# placa_tampa.net
KiCad netlist of a schematic drawn in EAGLE
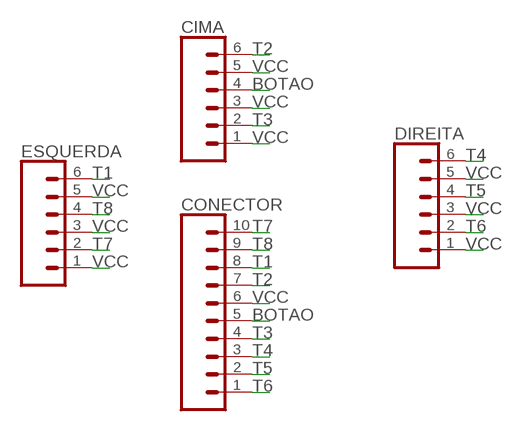
[diagram p0: schematic, sheet 1]

(export (version "E")
  (design (tool "Eeschema 10.0.6"))
  (components
    (comp (ref "CIMA")
      (value "CONN_06SILK_FEMALE_PTH")
      (footprint "eagle-import:1X06")
      (libsource (lib "eagle-import") (part "CONN_06SILK_FEMALE_PTH"))
    )
    (comp (ref "CONECTOR")
      (value "CONN_10\"")
      (footprint "eagle-import:1X10")
      (libsource (lib "eagle-import") (part "CONN_10{dblquote}"))
    )
    (comp (ref "DIREITA")
      (value "CONN_06SILK_FEMALE_PTH")
      (footprint "eagle-import:1X06")
      (libsource (lib "eagle-import") (part "CONN_06SILK_FEMALE_PTH"))
    )
    (comp (ref "ESQUERDA")
      (value "CONN_06SILK_FEMALE_PTH")
      (footprint "eagle-import:1X06")
      (libsource (lib "eagle-import") (part "CONN_06SILK_FEMALE_PTH"))
    )
  )
  (nets
    (net (code "1") (name "/BOTAO") (class "Default")
      (node (ref "CIMA") (pin "4") (pinfunction "4_4") (pintype "passive"))
      (node (ref "CONECTOR") (pin "5") (pinfunction "5_5") (pintype "passive"))
    )
    (net (code "2") (name "/T1") (class "Default")
      (node (ref "CONECTOR") (pin "8") (pinfunction "8_8") (pintype "passive"))
      (node (ref "ESQUERDA") (pin "6") (pinfunction "6_6") (pintype "passive"))
    )
    (net (code "3") (name "/T2") (class "Default")
      (node (ref "CIMA") (pin "6") (pinfunction "6_6") (pintype "passive"))
      (node (ref "CONECTOR") (pin "7") (pinfunction "7_7") (pintype "passive"))
    )
    (net (code "4") (name "/T3") (class "Default")
      (node (ref "CIMA") (pin "2") (pinfunction "2_2") (pintype "passive"))
      (node (ref "CONECTOR") (pin "4") (pinfunction "4_4") (pintype "passive"))
    )
    (net (code "5") (name "/T4") (class "Default")
      (node (ref "CONECTOR") (pin "3") (pinfunction "3_3") (pintype "passive"))
      (node (ref "DIREITA") (pin "6") (pinfunction "6_6") (pintype "passive"))
    )
    (net (code "6") (name "/T5") (class "Default")
      (node (ref "CONECTOR") (pin "2") (pinfunction "2_2") (pintype "passive"))
      (node (ref "DIREITA") (pin "4") (pinfunction "4_4") (pintype "passive"))
    )
    (net (code "7") (name "/T6") (class "Default")
      (node (ref "CONECTOR") (pin "1") (pinfunction "1_1") (pintype "passive"))
      (node (ref "DIREITA") (pin "2") (pinfunction "2_2") (pintype "passive"))
    )
    (net (code "8") (name "/T7") (class "Default")
      (node (ref "CONECTOR") (pin "10") (pinfunction "10_10") (pintype "passive"))
      (node (ref "ESQUERDA") (pin "2") (pinfunction "2_2") (pintype "passive"))
    )
    (net (code "9") (name "/T8") (class "Default")
      (node (ref "CONECTOR") (pin "9") (pinfunction "9_9") (pintype "passive"))
      (node (ref "ESQUERDA") (pin "4") (pinfunction "4_4") (pintype "passive"))
    )
    (net (code "10") (name "/VCC") (class "Default")
      (node (ref "CIMA") (pin "1") (pinfunction "1_1") (pintype "passive"))
      (node (ref "CIMA") (pin "3") (pinfunction "3_3") (pintype "passive"))
      (node (ref "CIMA") (pin "5") (pinfunction "5_5") (pintype "passive"))
      (node (ref "CONECTOR") (pin "6") (pinfunction "6_6") (pintype "passive"))
      (node (ref "DIREITA") (pin "1") (pinfunction "1_1") (pintype "passive"))
      (node (ref "DIREITA") (pin "3") (pinfunction "3_3") (pintype "passive"))
      (node (ref "DIREITA") (pin "5") (pinfunction "5_5") (pintype "passive"))
      (node (ref "ESQUERDA") (pin "1") (pinfunction "1_1") (pintype "passive"))
      (node (ref "ESQUERDA") (pin "3") (pinfunction "3_3") (pintype "passive"))
      (node (ref "ESQUERDA") (pin "5") (pinfunction "5_5") (pintype "passive"))
    )
  )
)
